# legoPFremote.net
KiCad netlist of a schematic drawn in EAGLE
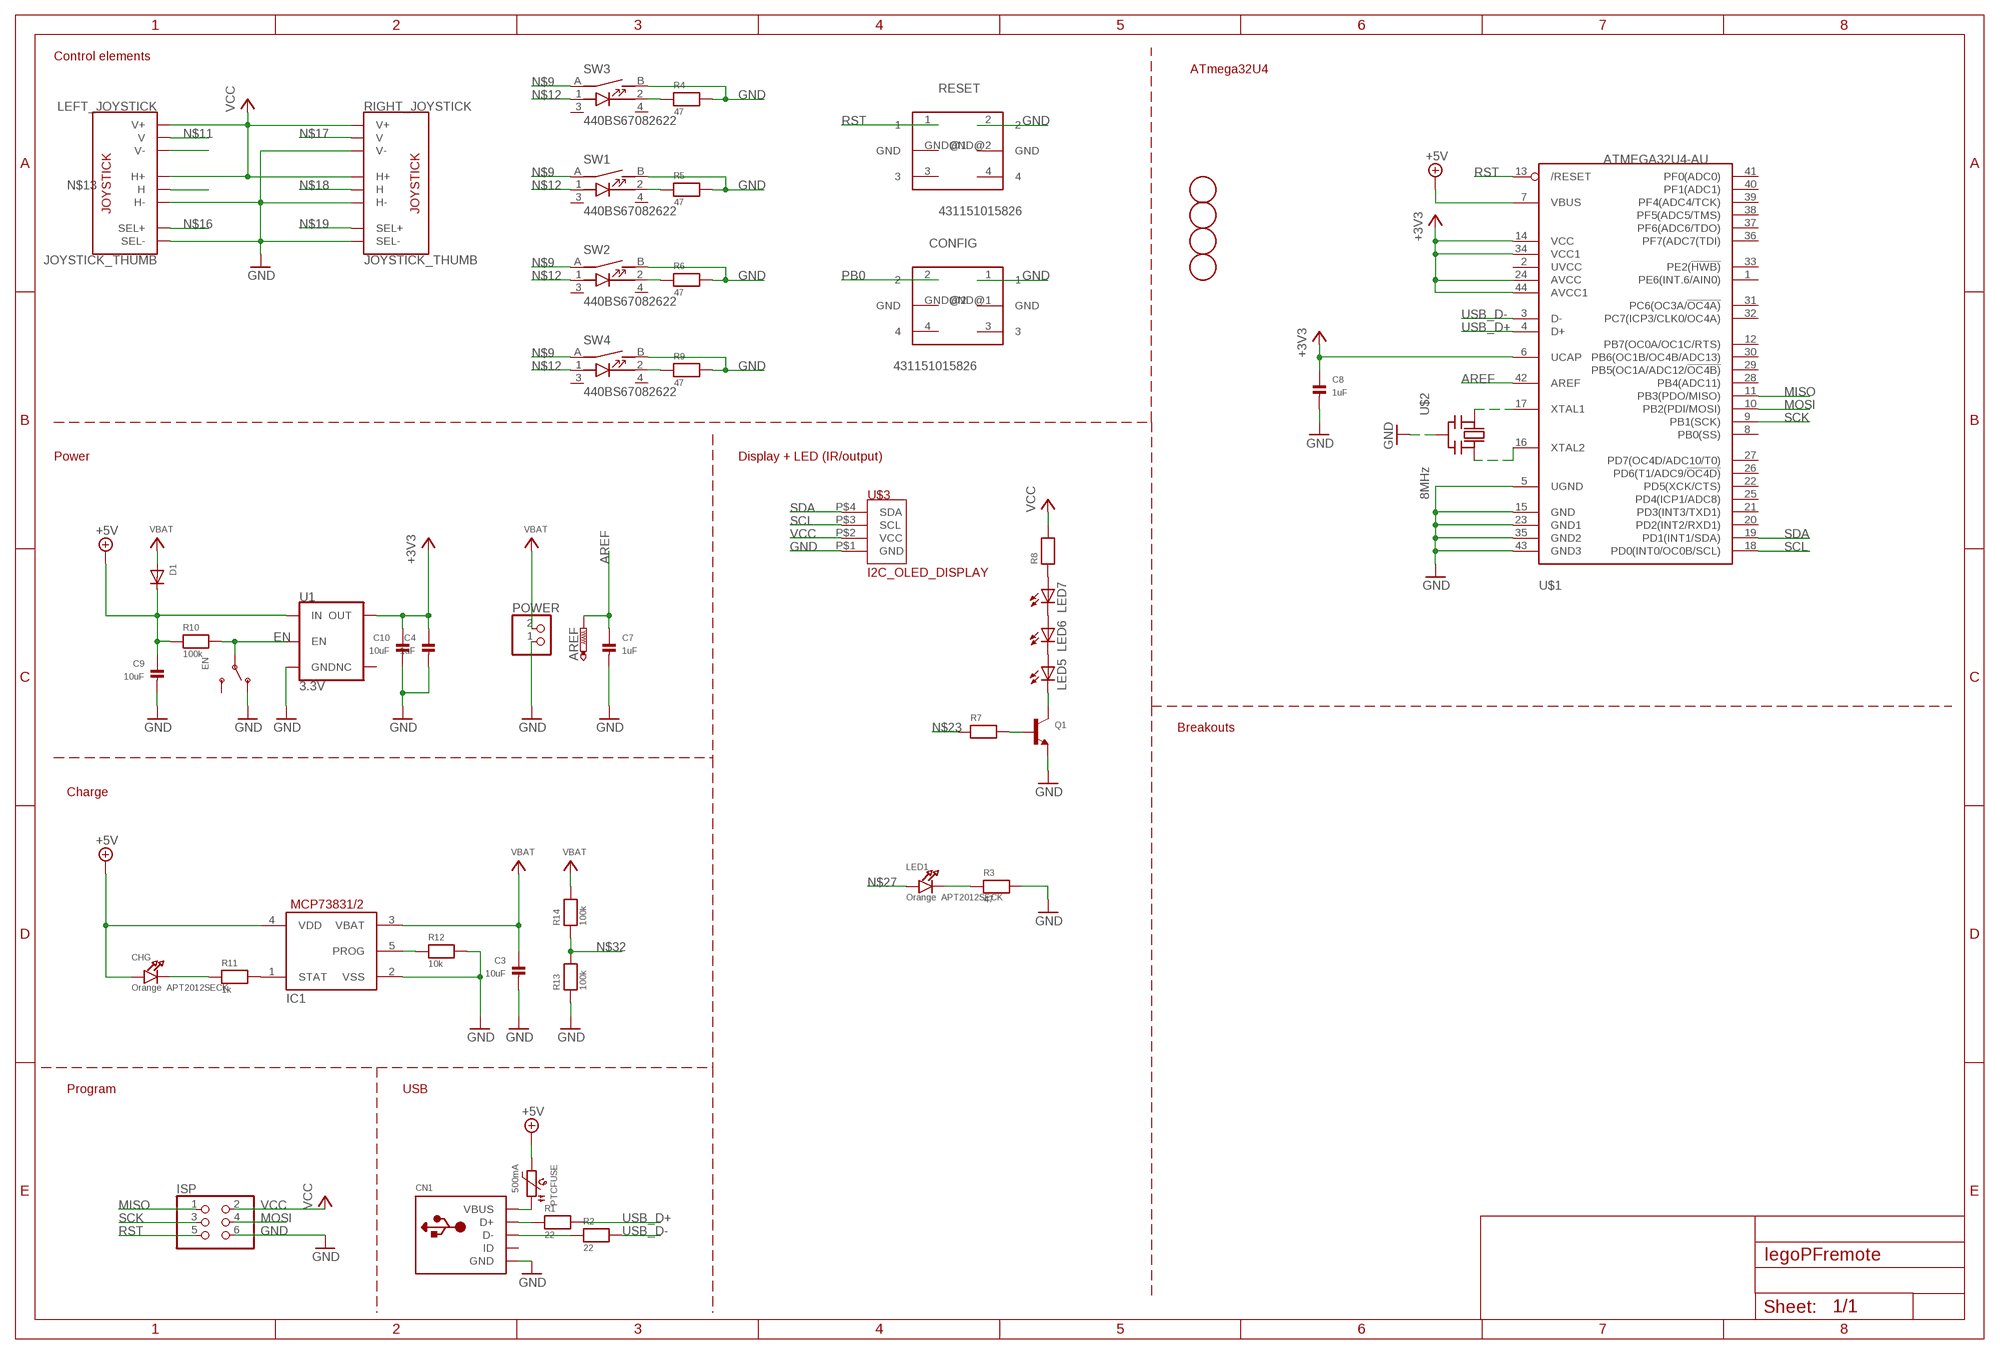
[diagram p0: schematic, sheet 1]

(export (version "E")
  (design (tool "Eeschema 10.0.6"))
  (components
    (comp (ref "AREF")
      (value "PTR1B1,27")
      (footprint "eagle-import:B1,27")
      (libsource (lib "eagle-import") (part "PTR1B1,27"))
    )
    (comp (ref "C3")
      (value "10uF")
      (footprint "eagle-import:0805")
      (libsource (lib "eagle-import") (part "CAP_CERAMIC0805"))
    )
    (comp (ref "C4")
      (value "1uF")
      (footprint "eagle-import:0805")
      (libsource (lib "eagle-import") (part "CAP_CERAMIC0805"))
    )
    (comp (ref "C7")
      (value "1uF")
      (footprint "eagle-import:0805")
      (libsource (lib "eagle-import") (part "CAP_CERAMIC0805"))
    )
    (comp (ref "C8")
      (value "1uF")
      (footprint "eagle-import:0805")
      (libsource (lib "eagle-import") (part "CAP_CERAMIC0805"))
    )
    (comp (ref "C9")
      (value "10uF")
      (footprint "eagle-import:0805")
      (libsource (lib "eagle-import") (part "CAP_CERAMIC0805"))
    )
    (comp (ref "C10")
      (value "10uF")
      (footprint "eagle-import:0805")
      (libsource (lib "eagle-import") (part "CAP_CERAMIC0805"))
    )
    (comp (ref "CHG")
      (value "Orange APT2012SECK")
      (footprint "eagle-import:CHIPLED_0805")
      (libsource (lib "eagle-import") (part "LED0805"))
    )
    (comp (ref "CN1")
      (value "USBMINIB")
      (footprint "eagle-import:USB-MINIB")
      (libsource (lib "eagle-import") (part "USBMINIB"))
    )
    (comp (ref "CONFIG")
      (value "431151015826")
      (footprint "eagle-import:431181015816")
      (libsource (lib "eagle-import") (part "431151015826"))
    )
    (comp (ref "D1")
      (value "DIODESOD-123")
      (footprint "eagle-import:SOD-123")
      (libsource (lib "eagle-import") (part "DIODESOD-123"))
    )
    (comp (ref "EN")
      (value "SWITCH_SPDT")
      (footprint "eagle-import:SPDT_SMT_SSSS811101")
      (libsource (lib "eagle-import") (part "SWITCH_SPDT"))
    )
    (comp (ref "IC1")
      (value "MCP73831/OT")
      (footprint "eagle-import:SOT23-5L")
      (libsource (lib "eagle-import") (part "MCP73831/OT"))
    )
    (comp (ref "ISP")
      (value "PINHD-2X3")
      (footprint "eagle-import:2X03")
      (libsource (lib "eagle-import") (part "PINHD-2X3"))
    )
    (comp (ref "LED1")
      (value "Orange APT2012SECK")
      (footprint "eagle-import:CHIPLED_0805")
      (libsource (lib "eagle-import") (part "LED0805"))
    )
    (comp (ref "LED5")
      (value "LEDIRL80A")
      (footprint "eagle-import:IRL80A")
      (libsource (lib "eagle-import") (part "LEDIRL80A"))
    )
    (comp (ref "LED6")
      (value "LEDIRL80A")
      (footprint "eagle-import:IRL80A")
      (libsource (lib "eagle-import") (part "LEDIRL80A"))
    )
    (comp (ref "LED7")
      (value "LEDIRL80A")
      (footprint "eagle-import:IRL80A")
      (libsource (lib "eagle-import") (part "LEDIRL80A"))
    )
    (comp (ref "LEFT_JOYSTICK")
      (value "JOYSTICK_THUMB")
      (footprint "eagle-import:JOYSTICK")
      (libsource (lib "eagle-import") (part "JOYSTICK_THUMB"))
    )
    (comp (ref "POWER")
      (value "JST_2PIN-THM")
      (footprint "eagle-import:JST-PH-2-THM")
      (libsource (lib "eagle-import") (part "JST_2PIN-THM"))
    )
    (comp (ref "PTCFUSE")
      (value "500mA")
      (footprint "eagle-import:1206")
      (libsource (lib "eagle-import") (part "PTC1206"))
    )
    (comp (ref "Q1")
      (value "TRANSISTOR_NPN")
      (footprint "eagle-import:SOT23-R")
      (libsource (lib "eagle-import") (part "TRANSISTOR_NPN"))
    )
    (comp (ref "R1")
      (value "22")
      (footprint "eagle-import:0805")
      (libsource (lib "eagle-import") (part "RESISTOR0805"))
    )
    (comp (ref "R2")
      (value "22")
      (footprint "eagle-import:0805")
      (libsource (lib "eagle-import") (part "RESISTOR0805"))
    )
    (comp (ref "R3")
      (value "47")
      (footprint "eagle-import:0805")
      (libsource (lib "eagle-import") (part "RESISTOR0805"))
    )
    (comp (ref "R4")
      (value "47")
      (footprint "eagle-import:0805")
      (libsource (lib "eagle-import") (part "RESISTOR0805"))
    )
    (comp (ref "R5")
      (value "47")
      (footprint "eagle-import:0805")
      (libsource (lib "eagle-import") (part "RESISTOR0805"))
    )
    (comp (ref "R6")
      (value "47")
      (footprint "eagle-import:0805")
      (libsource (lib "eagle-import") (part "RESISTOR0805"))
    )
    (comp (ref "R7")
      (value "RESISTOR0805")
      (footprint "eagle-import:0805")
      (libsource (lib "eagle-import") (part "RESISTOR0805"))
    )
    (comp (ref "R8")
      (value "RESISTOR0805")
      (footprint "eagle-import:0805")
      (libsource (lib "eagle-import") (part "RESISTOR0805"))
    )
    (comp (ref "R9")
      (value "47")
      (footprint "eagle-import:0805")
      (libsource (lib "eagle-import") (part "RESISTOR0805"))
    )
    (comp (ref "R10")
      (value "100k")
      (footprint "eagle-import:0805")
      (libsource (lib "eagle-import") (part "RESISTOR0805"))
    )
    (comp (ref "R11")
      (value "1k")
      (footprint "eagle-import:0805")
      (libsource (lib "eagle-import") (part "RESISTOR0805"))
    )
    (comp (ref "R12")
      (value "10k")
      (footprint "eagle-import:0805")
      (libsource (lib "eagle-import") (part "RESISTOR0805"))
    )
    (comp (ref "R13")
      (value "100k")
      (footprint "eagle-import:0805")
      (libsource (lib "eagle-import") (part "RESISTOR0805"))
    )
    (comp (ref "R14")
      (value "100k")
      (footprint "eagle-import:0805")
      (libsource (lib "eagle-import") (part "RESISTOR0805"))
    )
    (comp (ref "RESET")
      (value "431151015826")
      (footprint "eagle-import:431181015816")
      (libsource (lib "eagle-import") (part "431151015826"))
    )
    (comp (ref "RIGHT_JOYSTICK")
      (value "JOYSTICK_THUMB")
      (footprint "eagle-import:JOYSTICK")
      (libsource (lib "eagle-import") (part "JOYSTICK_THUMB"))
    )
    (comp (ref "SW1")
      (value "440BS67082622")
      (footprint "eagle-import:440BS67082622")
      (libsource (lib "eagle-import") (part "440BS67082622"))
    )
    (comp (ref "SW2")
      (value "440BS67082622")
      (footprint "eagle-import:440BS67082622")
      (libsource (lib "eagle-import") (part "440BS67082622"))
    )
    (comp (ref "SW3")
      (value "440BS67082622")
      (footprint "eagle-import:440BS67082622")
      (libsource (lib "eagle-import") (part "440BS67082622"))
    )
    (comp (ref "SW4")
      (value "440BS67082622")
      (footprint "eagle-import:440BS67082622")
      (libsource (lib "eagle-import") (part "440BS67082622"))
    )
    (comp (ref "U$1")
      (value "ATMEGA32U4-AU")
      (footprint "eagle-import:TQFP44")
      (libsource (lib "eagle-import") (part "ATMEGA32U4-AU"))
    )
    (comp (ref "U$2")
      (value "8MHz")
      (footprint "eagle-import:CSTCR-G")
      (libsource (lib "eagle-import") (part "CERMOSCILL-CSTCRG"))
    )
    (comp (ref "U$3")
      (value "I2C_OLED_DISPLAY")
      (footprint "eagle-import:HD1X4")
      (libsource (lib "eagle-import") (part "I2C_OLED_DISPLAY"))
    )
    (comp (ref "U$4")
      (value "MOUNTINGHOLE3.0THIN")
      (footprint "eagle-import:MOUNTINGHOLE_3.0_PLATEDTHIN")
      (libsource (lib "eagle-import") (part "MOUNTINGHOLE3.0THIN"))
    )
    (comp (ref "U$5")
      (value "MOUNTINGHOLE3.0THIN")
      (footprint "eagle-import:MOUNTINGHOLE_3.0_PLATEDTHIN")
      (libsource (lib "eagle-import") (part "MOUNTINGHOLE3.0THIN"))
    )
    (comp (ref "U$6")
      (value "MOUNTINGHOLE3.0THIN")
      (footprint "eagle-import:MOUNTINGHOLE_3.0_PLATEDTHIN")
      (libsource (lib "eagle-import") (part "MOUNTINGHOLE3.0THIN"))
    )
    (comp (ref "U$7")
      (value "MOUNTINGHOLE3.0THIN")
      (footprint "eagle-import:MOUNTINGHOLE_3.0_PLATEDTHIN")
      (libsource (lib "eagle-import") (part "MOUNTINGHOLE3.0THIN"))
    )
    (comp (ref "U1")
      (value "3.3V")
      (footprint "eagle-import:SOT23-5")
      (libsource (lib "eagle-import") (part "V_REG_AP2112K-3.3V"))
    )
  )
  (nets
    (net (code "1") (name "+3V3") (class "Default")
      (node (ref "C10") (pin "1") (pinfunction "P$1_1") (pintype "passive"))
      (node (ref "C4") (pin "1") (pinfunction "P$1_1") (pintype "passive"))
      (node (ref "C8") (pin "1") (pinfunction "P$1_1") (pintype "passive"))
      (node (ref "U$1") (pin "14") (pinfunction "VCC_14") (pintype "bidirectional"))
      (node (ref "U$1") (pin "24") (pinfunction "AVCC_24") (pintype "bidirectional"))
      (node (ref "U$1") (pin "34") (pinfunction "VCC1_34") (pintype "bidirectional"))
      (node (ref "U$1") (pin "44") (pinfunction "AVCC1_44") (pintype "bidirectional"))
      (node (ref "U$1") (pin "6") (pinfunction "UCAP_6") (pintype "bidirectional"))
      (node (ref "U1") (pin "5") (pinfunction "OUT_5") (pintype "passive"))
    )
    (net (code "2") (name "+5V") (class "Default")
      (node (ref "C9") (pin "1") (pinfunction "P$1_1") (pintype "passive"))
      (node (ref "CHG") (pin "A") (pinfunction "A_A") (pintype "passive"))
      (node (ref "D1") (pin "C") (pinfunction "C_C") (pintype "passive"))
      (node (ref "IC1") (pin "4") (pinfunction "VDD_4") (pintype "power_in"))
      (node (ref "PTCFUSE") (pin "2") (pinfunction "2_2") (pintype "passive"))
      (node (ref "R10") (pin "1") (pinfunction "1_1") (pintype "passive"))
      (node (ref "U$1") (pin "7") (pinfunction "VBUS_7") (pintype "bidirectional"))
      (node (ref "U1") (pin "1") (pinfunction "IN_1") (pintype "input"))
    )
    (net (code "3") (name "/AREF") (class "Default")
      (node (ref "AREF") (pin "TP") (pinfunction "TP_TP") (pintype "input"))
      (node (ref "C7") (pin "1") (pinfunction "P$1_1") (pintype "passive"))
      (node (ref "U$1") (pin "42") (pinfunction "AREF_42") (pintype "bidirectional"))
    )
    (net (code "4") (name "/EN") (class "Default")
      (node (ref "EN") (pin "B") (pinfunction "P_B") (pintype "passive"))
      (node (ref "R10") (pin "2") (pinfunction "2_2") (pintype "passive"))
      (node (ref "U1") (pin "3") (pinfunction "EN_3") (pintype "input"))
    )
    (net (code "5") (name "/MISO") (class "Default")
      (node (ref "ISP") (pin "1") (pinfunction "1_1") (pintype "passive"))
      (node (ref "U$1") (pin "11") (pinfunction "PB3(PDO/MISO)_11") (pintype "bidirectional"))
    )
    (net (code "6") (name "/MOSI") (class "Default")
      (node (ref "ISP") (pin "4") (pinfunction "4_4") (pintype "passive"))
      (node (ref "U$1") (pin "10") (pinfunction "PB2(PDI/MOSI)_10") (pintype "bidirectional"))
    )
    (net (code "7") (name "/N$9") (class "Default")
      (node (ref "SW1") (pin "A") (pinfunction "A_A") (pintype "passive"))
      (node (ref "SW2") (pin "A") (pinfunction "A_A") (pintype "passive"))
      (node (ref "SW3") (pin "A") (pinfunction "A_A") (pintype "passive"))
      (node (ref "SW4") (pin "A") (pinfunction "A_A") (pintype "passive"))
    )
    (net (code "8") (name "/N$11") (class "Default")
      (node (ref "LEFT_JOYSTICK") (pin "V2") (pinfunction "V_V2") (pintype "bidirectional"))
    )
    (net (code "9") (name "/N$12") (class "Default")
      (node (ref "SW1") (pin "1") (pinfunction "1_1") (pintype "passive"))
      (node (ref "SW2") (pin "1") (pinfunction "1_1") (pintype "passive"))
      (node (ref "SW3") (pin "1") (pinfunction "1_1") (pintype "passive"))
      (node (ref "SW4") (pin "1") (pinfunction "1_1") (pintype "passive"))
    )
    (net (code "10") (name "/N$13") (class "Default")
      (node (ref "LEFT_JOYSTICK") (pin "H2") (pinfunction "H_H2") (pintype "bidirectional"))
    )
    (net (code "11") (name "/N$16") (class "Default")
      (node (ref "LEFT_JOYSTICK") (pin "B1A") (pinfunction "SEL+_B1A") (pintype "bidirectional"))
    )
    (net (code "12") (name "/N$17") (class "Default")
      (node (ref "RIGHT_JOYSTICK") (pin "V2") (pinfunction "V_V2") (pintype "bidirectional"))
    )
    (net (code "13") (name "/N$18") (class "Default")
      (node (ref "RIGHT_JOYSTICK") (pin "H2") (pinfunction "H_H2") (pintype "bidirectional"))
    )
    (net (code "14") (name "/N$19") (class "Default")
      (node (ref "RIGHT_JOYSTICK") (pin "B1A") (pinfunction "SEL+_B1A") (pintype "bidirectional"))
    )
    (net (code "15") (name "/N$23") (class "Default")
      (node (ref "R7") (pin "1") (pinfunction "1_1") (pintype "passive"))
    )
    (net (code "16") (name "/N$27") (class "Default")
      (node (ref "LED1") (pin "A") (pinfunction "A_A") (pintype "passive"))
    )
    (net (code "17") (name "/N$32") (class "Default")
      (node (ref "R13") (pin "2") (pinfunction "2_2") (pintype "passive"))
      (node (ref "R14") (pin "1") (pinfunction "1_1") (pintype "passive"))
    )
    (net (code "18") (name "/PB0") (class "Default")
      (node (ref "CONFIG") (pin "2") (pinfunction "2_2") (pintype "bidirectional"))
    )
    (net (code "19") (name "/RST") (class "Default")
      (node (ref "ISP") (pin "5") (pinfunction "5_5") (pintype "passive"))
      (node (ref "RESET") (pin "1") (pinfunction "1_1") (pintype "bidirectional"))
      (node (ref "U$1") (pin "13") (pinfunction "/RESET_13") (pintype "bidirectional"))
    )
    (net (code "20") (name "/SCK") (class "Default")
      (node (ref "ISP") (pin "3") (pinfunction "3_3") (pintype "passive"))
      (node (ref "U$1") (pin "9") (pinfunction "PB1(SCK)_9") (pintype "bidirectional"))
    )
    (net (code "21") (name "/SCL") (class "Default")
      (node (ref "U$1") (pin "18") (pinfunction "PD0(INT0/OC0B/SCL)_18") (pintype "bidirectional"))
      (node (ref "U$3") (pin "P$3") (pinfunction "SCL_P$3") (pintype "bidirectional"))
    )
    (net (code "22") (name "/SDA") (class "Default")
      (node (ref "U$1") (pin "19") (pinfunction "PD1(INT1/SDA)_19") (pintype "bidirectional"))
      (node (ref "U$3") (pin "P$4") (pinfunction "SDA_P$4") (pintype "bidirectional"))
    )
    (net (code "23") (name "/USB_D+") (class "Default")
      (node (ref "R1") (pin "2") (pinfunction "2_2") (pintype "passive"))
      (node (ref "U$1") (pin "4") (pinfunction "D+_4") (pintype "bidirectional"))
    )
    (net (code "24") (name "/USB_D-") (class "Default")
      (node (ref "R2") (pin "2") (pinfunction "2_2") (pintype "passive"))
      (node (ref "U$1") (pin "3") (pinfunction "D-_3") (pintype "bidirectional"))
    )
    (net (code "25") (name "GND") (class "Default")
      (node (ref "C10") (pin "2") (pinfunction "P$2_2") (pintype "passive"))
      (node (ref "C3") (pin "2") (pinfunction "P$2_2") (pintype "passive"))
      (node (ref "C4") (pin "2") (pinfunction "P$2_2") (pintype "passive"))
      (node (ref "C7") (pin "2") (pinfunction "P$2_2") (pintype "passive"))
      (node (ref "C8") (pin "2") (pinfunction "P$2_2") (pintype "passive"))
      (node (ref "C9") (pin "2") (pinfunction "P$2_2") (pintype "passive"))
      (node (ref "CN1") (pin "GND") (pinfunction "GND_GND") (pintype "power_in"))
      (node (ref "CONFIG") (pin "1") (pinfunction "1_1") (pintype "bidirectional"))
      (node (ref "EN") (pin "A") (pinfunction "O_A") (pintype "passive"))
      (node (ref "IC1") (pin "2") (pinfunction "VSS_2") (pintype "power_in"))
      (node (ref "ISP") (pin "6") (pinfunction "6_6") (pintype "passive"))
      (node (ref "LEFT_JOYSTICK") (pin "B2A") (pinfunction "SEL-_B2A") (pintype "bidirectional"))
      (node (ref "LEFT_JOYSTICK") (pin "H3") (pinfunction "H-_H3") (pintype "bidirectional"))
      (node (ref "POWER") (pin "1") (pinfunction "2_1") (pintype "passive"))
      (node (ref "Q1") (pin "2") (pinfunction "E_2") (pintype "passive"))
      (node (ref "R12") (pin "2") (pinfunction "2_2") (pintype "passive"))
      (node (ref "R13") (pin "1") (pinfunction "1_1") (pintype "passive"))
      (node (ref "R3") (pin "2") (pinfunction "2_2") (pintype "passive"))
      (node (ref "R4") (pin "2") (pinfunction "2_2") (pintype "passive"))
      (node (ref "R5") (pin "2") (pinfunction "2_2") (pintype "passive"))
      (node (ref "R6") (pin "2") (pinfunction "2_2") (pintype "passive"))
      (node (ref "R9") (pin "2") (pinfunction "2_2") (pintype "passive"))
      (node (ref "RESET") (pin "2") (pinfunction "2_2") (pintype "bidirectional"))
      (node (ref "RIGHT_JOYSTICK") (pin "B2A") (pinfunction "SEL-_B2A") (pintype "bidirectional"))
      (node (ref "RIGHT_JOYSTICK") (pin "H3") (pinfunction "H-_H3") (pintype "bidirectional"))
      (node (ref "RIGHT_JOYSTICK") (pin "V3") (pinfunction "V-_V3") (pintype "bidirectional"))
      (node (ref "SW1") (pin "B") (pinfunction "B_B") (pintype "passive"))
      (node (ref "SW2") (pin "B") (pinfunction "B_B") (pintype "passive"))
      (node (ref "SW3") (pin "B") (pinfunction "B_B") (pintype "passive"))
      (node (ref "SW4") (pin "B") (pinfunction "B_B") (pintype "passive"))
      (node (ref "U$1") (pin "15") (pinfunction "GND_15") (pintype "bidirectional"))
      (node (ref "U$1") (pin "23") (pinfunction "GND1_23") (pintype "bidirectional"))
      (node (ref "U$1") (pin "35") (pinfunction "GND2_35") (pintype "bidirectional"))
      (node (ref "U$1") (pin "43") (pinfunction "GND3_43") (pintype "bidirectional"))
      (node (ref "U$1") (pin "5") (pinfunction "UGND_5") (pintype "bidirectional"))
      (node (ref "U$2") (pin "2") (pinfunction "GND_2") (pintype "bidirectional"))
      (node (ref "U$3") (pin "P$1") (pinfunction "GND_P$1") (pintype "bidirectional"))
      (node (ref "U1") (pin "2") (pinfunction "GND_2") (pintype "input"))
    )
    (net (code "26") (name "Net-(CHG-PadC)") (class "Default")
      (node (ref "CHG") (pin "C") (pinfunction "C_C") (pintype "passive"))
      (node (ref "R11") (pin "1") (pinfunction "1_1") (pintype "passive"))
    )
    (net (code "27") (name "Net-(CN1-PadD+)") (class "Default")
      (node (ref "CN1") (pin "D+") (pinfunction "D+_D+") (pintype "bidirectional"))
      (node (ref "R1") (pin "1") (pinfunction "1_1") (pintype "passive"))
    )
    (net (code "28") (name "Net-(CN1-PadD-)") (class "Default")
      (node (ref "CN1") (pin "D-") (pinfunction "D-_D-") (pintype "bidirectional"))
      (node (ref "R2") (pin "1") (pinfunction "1_1") (pintype "passive"))
    )
    (net (code "29") (name "Net-(CN1-PadVBUS)") (class "Default")
      (node (ref "CN1") (pin "VBUS") (pinfunction "VBUS_VBUS") (pintype "power_in"))
      (node (ref "PTCFUSE") (pin "1") (pinfunction "1_1") (pintype "passive"))
    )
    (net (code "30") (name "Net-(IC1-PROG)") (class "Default")
      (node (ref "IC1") (pin "5") (pinfunction "PROG_5") (pintype "input"))
      (node (ref "R12") (pin "1") (pinfunction "1_1") (pintype "passive"))
    )
    (net (code "31") (name "Net-(IC1-STAT)") (class "Default")
      (node (ref "IC1") (pin "1") (pinfunction "STAT_1") (pintype "output"))
      (node (ref "R11") (pin "2") (pinfunction "2_2") (pintype "passive"))
    )
    (net (code "32") (name "Net-(LED1-PadC)") (class "Default")
      (node (ref "LED1") (pin "C") (pinfunction "C_C") (pintype "passive"))
      (node (ref "R3") (pin "1") (pinfunction "1_1") (pintype "passive"))
    )
    (net (code "33") (name "Net-(LED5-C)") (class "Default")
      (node (ref "LED5") (pin "K") (pinfunction "C_K") (pintype "passive"))
      (node (ref "Q1") (pin "3") (pinfunction "C_3") (pintype "passive"))
    )
    (net (code "34") (name "Net-(LED6-C)") (class "Default")
      (node (ref "LED5") (pin "A") (pinfunction "A_A") (pintype "passive"))
      (node (ref "LED6") (pin "K") (pinfunction "C_K") (pintype "passive"))
    )
    (net (code "35") (name "Net-(LED7-C)") (class "Default")
      (node (ref "LED6") (pin "A") (pinfunction "A_A") (pintype "passive"))
      (node (ref "LED7") (pin "K") (pinfunction "C_K") (pintype "passive"))
    )
    (net (code "36") (name "Net-(LED7-PadA)") (class "Default")
      (node (ref "LED7") (pin "A") (pinfunction "A_A") (pintype "passive"))
      (node (ref "R8") (pin "1") (pinfunction "1_1") (pintype "passive"))
    )
    (net (code "37") (name "Net-(Q1-B)") (class "Default")
      (node (ref "Q1") (pin "1") (pinfunction "B_1") (pintype "passive"))
      (node (ref "R7") (pin "2") (pinfunction "2_2") (pintype "passive"))
    )
    (net (code "38") (name "Net-(R4-Pad1)") (class "Default")
      (node (ref "R4") (pin "1") (pinfunction "1_1") (pintype "passive"))
      (node (ref "SW3") (pin "2") (pinfunction "2_2") (pintype "passive"))
    )
    (net (code "39") (name "Net-(R5-Pad1)") (class "Default")
      (node (ref "R5") (pin "1") (pinfunction "1_1") (pintype "passive"))
      (node (ref "SW1") (pin "2") (pinfunction "2_2") (pintype "passive"))
    )
    (net (code "40") (name "Net-(R6-Pad1)") (class "Default")
      (node (ref "R6") (pin "1") (pinfunction "1_1") (pintype "passive"))
      (node (ref "SW2") (pin "2") (pinfunction "2_2") (pintype "passive"))
    )
    (net (code "41") (name "Net-(R9-Pad1)") (class "Default")
      (node (ref "R9") (pin "1") (pinfunction "1_1") (pintype "passive"))
      (node (ref "SW4") (pin "2") (pinfunction "2_2") (pintype "passive"))
    )
    (net (code "42") (name "Net-(U$1-XTAL1)") (class "Default")
      (node (ref "U$1") (pin "17") (pinfunction "XTAL1_17") (pintype "bidirectional"))
      (node (ref "U$2") (pin "1") (pinfunction "IN_1") (pintype "bidirectional"))
    )
    (net (code "43") (name "Net-(U$1-XTAL2)") (class "Default")
      (node (ref "U$1") (pin "16") (pinfunction "XTAL2_16") (pintype "bidirectional"))
      (node (ref "U$2") (pin "3") (pinfunction "OUT_3") (pintype "bidirectional"))
    )
    (net (code "44") (name "VBAT") (class "Default")
      (node (ref "C3") (pin "1") (pinfunction "P$1_1") (pintype "passive"))
      (node (ref "D1") (pin "A") (pinfunction "A_A") (pintype "passive"))
      (node (ref "IC1") (pin "3") (pinfunction "VBAT_3") (pintype "bidirectional"))
      (node (ref "POWER") (pin "2") (pinfunction "1_2") (pintype "passive"))
      (node (ref "R14") (pin "2") (pinfunction "2_2") (pintype "passive"))
    )
    (net (code "45") (name "VCC") (class "Default")
      (node (ref "ISP") (pin "2") (pinfunction "2_2") (pintype "passive"))
      (node (ref "LEFT_JOYSTICK") (pin "H1") (pinfunction "H+_H1") (pintype "bidirectional"))
      (node (ref "LEFT_JOYSTICK") (pin "V1") (pinfunction "V+_V1") (pintype "bidirectional"))
      (node (ref "R8") (pin "2") (pinfunction "2_2") (pintype "passive"))
      (node (ref "RIGHT_JOYSTICK") (pin "H1") (pinfunction "H+_H1") (pintype "bidirectional"))
      (node (ref "RIGHT_JOYSTICK") (pin "V1") (pinfunction "V+_V1") (pintype "bidirectional"))
      (node (ref "U$3") (pin "P$2") (pinfunction "VCC_P$2") (pintype "bidirectional"))
    )
    (net (code "46") (name "unconnected-(CN1-PadID)") (class "Default")
      (node (ref "CN1") (pin "ID") (pinfunction "ID_ID") (pintype "bidirectional"))
    )
    (net (code "47") (name "unconnected-(CONFIG-GND-PadGND@1)") (class "Default")
      (node (ref "CONFIG") (pin "GND@1") (pinfunction "GND_GND@1") (pintype "bidirectional"))
    )
    (net (code "48") (name "unconnected-(CONFIG-GND-PadGND@2)") (class "Default")
      (node (ref "CONFIG") (pin "GND@2") (pinfunction "GND_GND@2") (pintype "bidirectional"))
    )
    (net (code "49") (name "unconnected-(CONFIG-Pad3)") (class "Default")
      (node (ref "CONFIG") (pin "3") (pinfunction "3_3") (pintype "bidirectional"))
    )
    (net (code "50") (name "unconnected-(CONFIG-Pad4)") (class "Default")
      (node (ref "CONFIG") (pin "4") (pinfunction "4_4") (pintype "bidirectional"))
    )
    (net (code "51") (name "unconnected-(EN-S-PadC)") (class "Default")
      (node (ref "EN") (pin "C") (pinfunction "S_C") (pintype "passive"))
    )
    (net (code "52") (name "unconnected-(LEFT_JOYSTICK-V--PadV3)") (class "Default")
      (node (ref "LEFT_JOYSTICK") (pin "V3") (pinfunction "V-_V3") (pintype "bidirectional"))
    )
    (net (code "53") (name "unconnected-(RESET-GND-PadGND@1)") (class "Default")
      (node (ref "RESET") (pin "GND@1") (pinfunction "GND_GND@1") (pintype "bidirectional"))
    )
    (net (code "54") (name "unconnected-(RESET-GND-PadGND@2)") (class "Default")
      (node (ref "RESET") (pin "GND@2") (pinfunction "GND_GND@2") (pintype "bidirectional"))
    )
    (net (code "55") (name "unconnected-(RESET-Pad3)") (class "Default")
      (node (ref "RESET") (pin "3") (pinfunction "3_3") (pintype "bidirectional"))
    )
    (net (code "56") (name "unconnected-(RESET-Pad4)") (class "Default")
      (node (ref "RESET") (pin "4") (pinfunction "4_4") (pintype "bidirectional"))
    )
    (net (code "57") (name "unconnected-(SW1-Pad3)") (class "Default")
      (node (ref "SW1") (pin "3") (pinfunction "3_3") (pintype "no_connect"))
    )
    (net (code "58") (name "unconnected-(SW1-Pad4)") (class "Default")
      (node (ref "SW1") (pin "4") (pinfunction "4_4") (pintype "no_connect"))
    )
    (net (code "59") (name "unconnected-(SW2-Pad3)") (class "Default")
      (node (ref "SW2") (pin "3") (pinfunction "3_3") (pintype "no_connect"))
    )
    (net (code "60") (name "unconnected-(SW2-Pad4)") (class "Default")
      (node (ref "SW2") (pin "4") (pinfunction "4_4") (pintype "no_connect"))
    )
    (net (code "61") (name "unconnected-(SW3-Pad3)") (class "Default")
      (node (ref "SW3") (pin "3") (pinfunction "3_3") (pintype "no_connect"))
    )
    (net (code "62") (name "unconnected-(SW3-Pad4)") (class "Default")
      (node (ref "SW3") (pin "4") (pinfunction "4_4") (pintype "no_connect"))
    )
    (net (code "63") (name "unconnected-(SW4-Pad3)") (class "Default")
      (node (ref "SW4") (pin "3") (pinfunction "3_3") (pintype "no_connect"))
    )
    (net (code "64") (name "unconnected-(SW4-Pad4)") (class "Default")
      (node (ref "SW4") (pin "4") (pinfunction "4_4") (pintype "no_connect"))
    )
    (net (code "65") (name "unconnected-(U$1-PB0(SS)-Pad8)") (class "Default")
      (node (ref "U$1") (pin "8") (pinfunction "PB0(SS)_8") (pintype "bidirectional"))
    )
    (net (code "66") (name "unconnected-(U$1-PB4(ADC11)-Pad28)") (class "Default")
      (node (ref "U$1") (pin "28") (pinfunction "PB4(ADC11)_28") (pintype "bidirectional"))
    )
    (net (code "67") (name "unconnected-(U$1-PB5(OC1A{slash}ADC12{slash}~{OC4B})-Pad29)") (class "Default")
      (node (ref "U$1") (pin "29") (pinfunction "PB5(OC1A/ADC12/~{OC4B})_29") (pintype "bidirectional"))
    )
    (net (code "68") (name "unconnected-(U$1-PB6(OC1B{slash}OC4B{slash}ADC13)-Pad30)") (class "Default")
      (node (ref "U$1") (pin "30") (pinfunction "PB6(OC1B/OC4B/ADC13)_30") (pintype "bidirectional"))
    )
    (net (code "69") (name "unconnected-(U$1-PB7(OC0A{slash}OC1C{slash}RTS)-Pad12)") (class "Default")
      (node (ref "U$1") (pin "12") (pinfunction "PB7(OC0A/OC1C/RTS)_12") (pintype "bidirectional"))
    )
    (net (code "70") (name "unconnected-(U$1-PC6(OC3A{slash}~{OC4A})-Pad31)") (class "Default")
      (node (ref "U$1") (pin "31") (pinfunction "PC6(OC3A/~{OC4A})_31") (pintype "bidirectional"))
    )
    (net (code "71") (name "unconnected-(U$1-PC7(ICP3{slash}CLK0{slash}OC4A)-Pad32)") (class "Default")
      (node (ref "U$1") (pin "32") (pinfunction "PC7(ICP3/CLK0/OC4A)_32") (pintype "bidirectional"))
    )
    (net (code "72") (name "unconnected-(U$1-PD2(INT2{slash}RXD1)-Pad20)") (class "Default")
      (node (ref "U$1") (pin "20") (pinfunction "PD2(INT2/RXD1)_20") (pintype "bidirectional"))
    )
    (net (code "73") (name "unconnected-(U$1-PD3(INT3{slash}TXD1)-Pad21)") (class "Default")
      (node (ref "U$1") (pin "21") (pinfunction "PD3(INT3/TXD1)_21") (pintype "bidirectional"))
    )
    (net (code "74") (name "unconnected-(U$1-PD4(ICP1{slash}ADC8)-Pad25)") (class "Default")
      (node (ref "U$1") (pin "25") (pinfunction "PD4(ICP1/ADC8)_25") (pintype "bidirectional"))
    )
    (net (code "75") (name "unconnected-(U$1-PD5(XCK{slash}CTS)-Pad22)") (class "Default")
      (node (ref "U$1") (pin "22") (pinfunction "PD5(XCK/CTS)_22") (pintype "bidirectional"))
    )
    (net (code "76") (name "unconnected-(U$1-PD6(T1{slash}ADC9{slash}~{OC4D})-Pad26)") (class "Default")
      (node (ref "U$1") (pin "26") (pinfunction "PD6(T1/ADC9/~{OC4D})_26") (pintype "bidirectional"))
    )
    (net (code "77") (name "unconnected-(U$1-PD7(OC4D{slash}ADC10{slash}T0)-Pad27)") (class "Default")
      (node (ref "U$1") (pin "27") (pinfunction "PD7(OC4D/ADC10/T0)_27") (pintype "bidirectional"))
    )
    (net (code "78") (name "unconnected-(U$1-PE2(~{HWB})-Pad33)") (class "Default")
      (node (ref "U$1") (pin "33") (pinfunction "PE2(~{HWB})_33") (pintype "bidirectional"))
    )
    (net (code "79") (name "unconnected-(U$1-PE6(INT.6{slash}AIN0)-Pad1)") (class "Default")
      (node (ref "U$1") (pin "1") (pinfunction "PE6(INT.6/AIN0)_1") (pintype "bidirectional"))
    )
    (net (code "80") (name "unconnected-(U$1-PF0(ADC0)-Pad41)") (class "Default")
      (node (ref "U$1") (pin "41") (pinfunction "PF0(ADC0)_41") (pintype "bidirectional"))
    )
    (net (code "81") (name "unconnected-(U$1-PF1(ADC1)-Pad40)") (class "Default")
      (node (ref "U$1") (pin "40") (pinfunction "PF1(ADC1)_40") (pintype "bidirectional"))
    )
    (net (code "82") (name "unconnected-(U$1-PF4(ADC4{slash}TCK)-Pad39)") (class "Default")
      (node (ref "U$1") (pin "39") (pinfunction "PF4(ADC4/TCK)_39") (pintype "bidirectional"))
    )
    (net (code "83") (name "unconnected-(U$1-PF5(ADC5{slash}TMS)-Pad38)") (class "Default")
      (node (ref "U$1") (pin "38") (pinfunction "PF5(ADC5/TMS)_38") (pintype "bidirectional"))
    )
    (net (code "84") (name "unconnected-(U$1-PF6(ADC6{slash}TDO)-Pad37)") (class "Default")
      (node (ref "U$1") (pin "37") (pinfunction "PF6(ADC6/TDO)_37") (pintype "bidirectional"))
    )
    (net (code "85") (name "unconnected-(U$1-PF7(ADC7(TDI)-Pad36)") (class "Default")
      (node (ref "U$1") (pin "36") (pinfunction "PF7(ADC7(TDI)_36") (pintype "bidirectional"))
    )
    (net (code "86") (name "unconnected-(U$1-UVCC-Pad2)") (class "Default")
      (node (ref "U$1") (pin "2") (pinfunction "UVCC_2") (pintype "bidirectional"))
    )
    (net (code "87") (name "unconnected-(U1-NC-Pad4)") (class "Default")
      (node (ref "U1") (pin "4") (pinfunction "NC_4") (pintype "no_connect"))
    )
  )
)
